# Philbrick.net
KiCad netlist of a schematic drawn in EAGLE
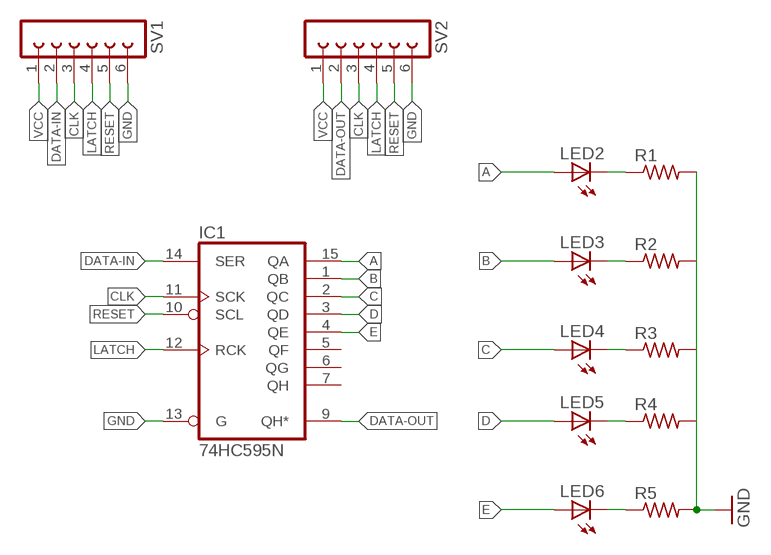
[diagram p0: schematic, sheet 1]

(export (version "E")
  (design (tool "Eeschema 10.0.6"))
  (components
    (comp (ref "IC1")
      (value "74HC595N")
      (footprint "eagle-import:DIL16")
      (libsource (lib "eagle-import") (part "74595NHC"))
    )
    (comp (ref "LED2")
      (value "LED5MM")
      (footprint "eagle-import:LED5MM")
      (libsource (lib "eagle-import") (part "LED5MM"))
    )
    (comp (ref "LED3")
      (value "LED5MM")
      (footprint "eagle-import:LED5MM")
      (libsource (lib "eagle-import") (part "LED5MM"))
    )
    (comp (ref "LED4")
      (value "LED5MM")
      (footprint "eagle-import:LED5MM")
      (libsource (lib "eagle-import") (part "LED5MM"))
    )
    (comp (ref "LED5")
      (value "LED5MM")
      (footprint "eagle-import:LED5MM")
      (libsource (lib "eagle-import") (part "LED5MM"))
    )
    (comp (ref "LED6")
      (value "LED5MM")
      (footprint "eagle-import:LED5MM")
      (libsource (lib "eagle-import") (part "LED5MM"))
    )
    (comp (ref "R1")
      (value "R-US_0204/7")
      (footprint "eagle-import:0204_7")
      (libsource (lib "eagle-import") (part "R-US_0204/7"))
    )
    (comp (ref "R2")
      (value "R-US_0204/7")
      (footprint "eagle-import:0204_7")
      (libsource (lib "eagle-import") (part "R-US_0204/7"))
    )
    (comp (ref "R3")
      (value "R-US_0204/7")
      (footprint "eagle-import:0204_7")
      (libsource (lib "eagle-import") (part "R-US_0204/7"))
    )
    (comp (ref "R4")
      (value "R-US_0204/7")
      (footprint "eagle-import:0204_7")
      (libsource (lib "eagle-import") (part "R-US_0204/7"))
    )
    (comp (ref "R5")
      (value "R-US_0204/7")
      (footprint "eagle-import:0204_7")
      (libsource (lib "eagle-import") (part "R-US_0204/7"))
    )
    (comp (ref "SV1")
      (value "FE06-1")
      (footprint "eagle-import:FE06")
      (libsource (lib "eagle-import") (part "FE06-1"))
    )
    (comp (ref "SV2")
      (value "FE06-1")
      (footprint "eagle-import:FE06")
      (libsource (lib "eagle-import") (part "FE06-1"))
    )
  )
  (nets
    (net (code "1") (name "A") (class "Default")
      (node (ref "IC1") (pin "15") (pinfunction "QA_15") (pintype "tri_state"))
      (node (ref "LED2") (pin "A") (pinfunction "A_A") (pintype "passive"))
    )
    (net (code "2") (name "B") (class "Default")
      (node (ref "IC1") (pin "1") (pinfunction "QB_1") (pintype "tri_state"))
      (node (ref "LED3") (pin "A") (pinfunction "A_A") (pintype "passive"))
    )
    (net (code "3") (name "C") (class "Default")
      (node (ref "IC1") (pin "2") (pinfunction "QC_2") (pintype "tri_state"))
      (node (ref "LED4") (pin "A") (pinfunction "A_A") (pintype "passive"))
    )
    (net (code "4") (name "CLK") (class "Default")
      (node (ref "IC1") (pin "11") (pinfunction "SCK_11") (pintype "input"))
      (node (ref "SV1") (pin "3") (pinfunction "3_3") (pintype "passive"))
      (node (ref "SV2") (pin "3") (pinfunction "3_3") (pintype "passive"))
    )
    (net (code "5") (name "D") (class "Default")
      (node (ref "IC1") (pin "3") (pinfunction "QD_3") (pintype "tri_state"))
      (node (ref "LED5") (pin "A") (pinfunction "A_A") (pintype "passive"))
    )
    (net (code "6") (name "DATA-IN") (class "Default")
      (node (ref "IC1") (pin "14") (pinfunction "SER_14") (pintype "input"))
      (node (ref "SV1") (pin "2") (pinfunction "2_2") (pintype "passive"))
    )
    (net (code "7") (name "DATA-OUT") (class "Default")
      (node (ref "IC1") (pin "9") (pinfunction "QH*_9") (pintype "tri_state"))
      (node (ref "SV2") (pin "2") (pinfunction "2_2") (pintype "passive"))
    )
    (net (code "8") (name "E") (class "Default")
      (node (ref "IC1") (pin "4") (pinfunction "QE_4") (pintype "tri_state"))
      (node (ref "LED6") (pin "A") (pinfunction "A_A") (pintype "passive"))
    )
    (net (code "9") (name "GND") (class "Default")
      (node (ref "IC1") (pin "13") (pinfunction "G_13") (pintype "input"))
      (node (ref "R1") (pin "2") (pinfunction "2_2") (pintype "passive"))
      (node (ref "R5") (pin "2") (pinfunction "2_2") (pintype "passive"))
      (node (ref "SV1") (pin "6") (pinfunction "6_6") (pintype "passive"))
      (node (ref "SV2") (pin "6") (pinfunction "6_6") (pintype "passive"))
    )
    (net (code "10") (name "LATCH") (class "Default")
      (node (ref "IC1") (pin "12") (pinfunction "RCK_12") (pintype "input"))
      (node (ref "SV1") (pin "4") (pinfunction "4_4") (pintype "passive"))
      (node (ref "SV2") (pin "4") (pinfunction "4_4") (pintype "passive"))
    )
    (net (code "11") (name "Net-(LED2-C)") (class "Default")
      (node (ref "LED2") (pin "K") (pinfunction "C_K") (pintype "passive"))
      (node (ref "R1") (pin "1") (pinfunction "1_1") (pintype "passive"))
    )
    (net (code "12") (name "Net-(LED3-C)") (class "Default")
      (node (ref "LED3") (pin "K") (pinfunction "C_K") (pintype "passive"))
      (node (ref "R2") (pin "1") (pinfunction "1_1") (pintype "passive"))
    )
    (net (code "13") (name "Net-(LED4-C)") (class "Default")
      (node (ref "LED4") (pin "K") (pinfunction "C_K") (pintype "passive"))
      (node (ref "R3") (pin "1") (pinfunction "1_1") (pintype "passive"))
    )
    (net (code "14") (name "Net-(LED5-C)") (class "Default")
      (node (ref "LED5") (pin "K") (pinfunction "C_K") (pintype "passive"))
      (node (ref "R4") (pin "1") (pinfunction "1_1") (pintype "passive"))
    )
    (net (code "15") (name "Net-(LED6-C)") (class "Default")
      (node (ref "LED6") (pin "K") (pinfunction "C_K") (pintype "passive"))
      (node (ref "R5") (pin "1") (pinfunction "1_1") (pintype "passive"))
    )
    (net (code "16") (name "RESET") (class "Default")
      (node (ref "IC1") (pin "10") (pinfunction "SCL_10") (pintype "input"))
      (node (ref "SV1") (pin "5") (pinfunction "5_5") (pintype "passive"))
      (node (ref "SV2") (pin "5") (pinfunction "5_5") (pintype "passive"))
    )
    (net (code "17") (name "VCC") (class "Default")
      (node (ref "SV1") (pin "1") (pinfunction "1_1") (pintype "passive"))
      (node (ref "SV2") (pin "1") (pinfunction "1_1") (pintype "passive"))
    )
    (net (code "18") (name "unconnected-(IC1A-QF-Pad5)") (class "Default")
      (node (ref "IC1") (pin "5") (pinfunction "QF_5") (pintype "tri_state"))
    )
    (net (code "19") (name "unconnected-(IC1A-QG-Pad6)") (class "Default")
      (node (ref "IC1") (pin "6") (pinfunction "QG_6") (pintype "tri_state"))
    )
    (net (code "20") (name "unconnected-(IC1A-QH-Pad7)") (class "Default")
      (node (ref "IC1") (pin "7") (pinfunction "QH_7") (pintype "tri_state"))
    )
    (net (code "21") (name "unconnected-(R2-Pad2)") (class "Default")
      (node (ref "R2") (pin "2") (pinfunction "2_2") (pintype "passive"))
    )
    (net (code "22") (name "unconnected-(R3-Pad2)") (class "Default")
      (node (ref "R3") (pin "2") (pinfunction "2_2") (pintype "passive"))
    )
    (net (code "23") (name "unconnected-(R4-Pad2)") (class "Default")
      (node (ref "R4") (pin "2") (pinfunction "2_2") (pintype "passive"))
    )
  )
)
